# Relay.net
KiCad netlist of a schematic drawn in Altium Designer
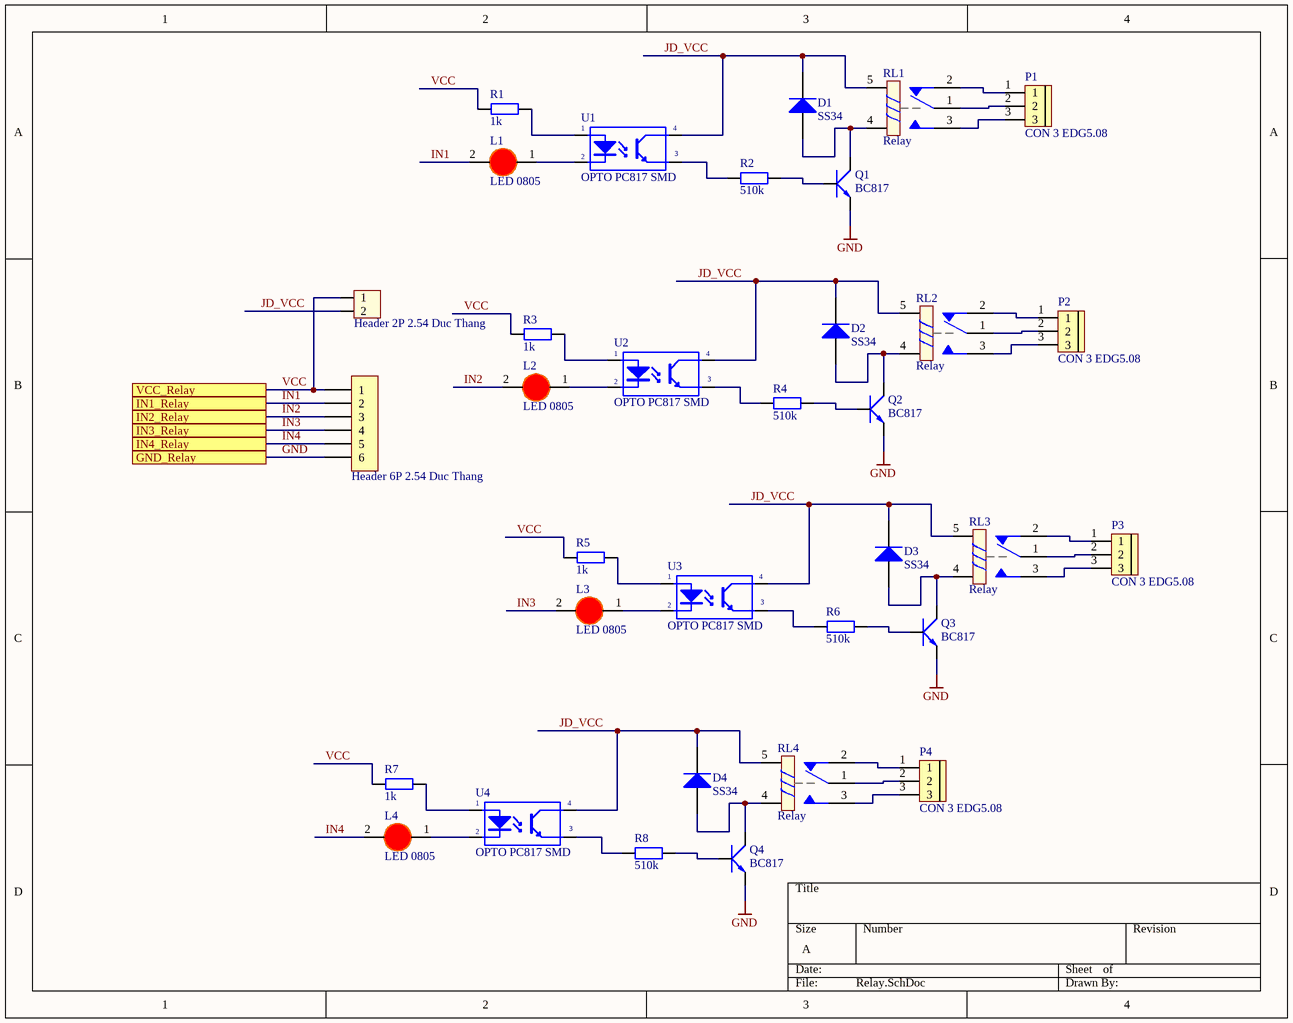
[diagram p0: Relay.SchDoc]

(export (version "E")
  (design (tool "Eeschema 10.0.6"))
  (components
    (comp (ref "D1")
      (value "SS34")
      (footprint "DIODE SMA")
      (description "Dán")
      (libsource (lib "Altium_Lib_by_KhueNguyenCreator") (part "Diode SS34 ( 1N5822 )"))
    )
    (comp (ref "D2")
      (value "SS34")
      (footprint "DIODE SMA")
      (description "Dán")
      (libsource (lib "Altium_Lib_by_KhueNguyenCreator") (part "Diode SS34 ( 1N5822 )"))
    )
    (comp (ref "D3")
      (value "SS34")
      (footprint "DIODE SMA")
      (description "Dán")
      (libsource (lib "Altium_Lib_by_KhueNguyenCreator") (part "Diode SS34 ( 1N5822 )"))
    )
    (comp (ref "D4")
      (value "SS34")
      (footprint "DIODE SMA")
      (description "Dán")
      (libsource (lib "Altium_Lib_by_KhueNguyenCreator") (part "Diode SS34 ( 1N5822 )"))
    )
    (comp (ref "H1")
      (value "Header 2P 2.54 Duc Thang")
      (footprint "XH2.54M-2")
      (description "Cắm")
      (libsource (lib "Altium_Lib_by_KhueNguyenCreator") (part "Header 2P 2.54 Duc Thang"))
    )
    (comp (ref "H2")
      (value "Header 6P 2.54 Duc Thang")
      (footprint "XH2.54M-6")
      (description "Cắm")
      (libsource (lib "Altium_Lib_by_KhueNguyenCreator") (part "Header 6P 2.54 Duc Thang"))
    )
    (comp (ref "L1")
      (value "LED 0805")
      (footprint "LED-0805-Red")
      (description "Dán")
      (libsource (lib "BKRES_Schlib") (part "LED 0805 Do"))
    )
    (comp (ref "L2")
      (value "LED 0805")
      (footprint "LED-0805-Red")
      (description "Dán")
      (libsource (lib "BKRES_Schlib") (part "LED 0805 Do"))
    )
    (comp (ref "L3")
      (value "LED 0805")
      (footprint "LED-0805-Red")
      (description "Dán")
      (libsource (lib "BKRES_Schlib") (part "LED 0805 Do"))
    )
    (comp (ref "L4")
      (value "LED 0805")
      (footprint "LED-0805-Red")
      (description "Dán")
      (libsource (lib "BKRES_Schlib") (part "LED 0805 Do"))
    )
    (comp (ref "P1")
      (value "CON 3 EDG5.08")
      (footprint "CON 3 3EDG5.08")
      (description "Cắm")
      (libsource (lib "Altium_Lib_by_KhueNguyenCreator") (part "CON 3 EDG5.08"))
    )
    (comp (ref "P2")
      (value "CON 3 EDG5.08")
      (footprint "CON 3 3EDG5.08")
      (description "Cắm")
      (libsource (lib "Altium_Lib_by_KhueNguyenCreator") (part "CON 3 EDG5.08"))
    )
    (comp (ref "P3")
      (value "CON 3 EDG5.08")
      (footprint "CON 3 3EDG5.08")
      (description "Cắm")
      (libsource (lib "Altium_Lib_by_KhueNguyenCreator") (part "CON 3 EDG5.08"))
    )
    (comp (ref "P4")
      (value "CON 3 EDG5.08")
      (footprint "CON 3 3EDG5.08")
      (description "Cắm")
      (libsource (lib "Altium_Lib_by_KhueNguyenCreator") (part "CON 3 EDG5.08"))
    )
    (comp (ref "Q1")
      (value "BC817")
      (footprint "SOT-23")
      (description "SOT-23 - C8658")
      (libsource (lib "Altium_Lib_by_KhueNguyenCreator") (part "Trans BC817"))
    )
    (comp (ref "Q2")
      (value "BC817")
      (footprint "SOT-23")
      (description "SOT-23 - C8658")
      (libsource (lib "Altium_Lib_by_KhueNguyenCreator") (part "Trans BC817"))
    )
    (comp (ref "Q3")
      (value "BC817")
      (footprint "SOT-23")
      (description "SOT-23 - C8658")
      (libsource (lib "Altium_Lib_by_KhueNguyenCreator") (part "Trans BC817"))
    )
    (comp (ref "Q4")
      (value "BC817")
      (footprint "SOT-23")
      (description "SOT-23 - C8658")
      (libsource (lib "Altium_Lib_by_KhueNguyenCreator") (part "Trans BC817"))
    )
    (comp (ref "R1")
      (value "1k")
      (footprint "tro smd 0805")
      (description "Dán")
      (libsource (lib "Altium_Lib_by_KhueNguyenCreator") (part "Tro 0805 1% 1k"))
    )
    (comp (ref "R2")
      (value "510k")
      (footprint "tro smd 0805")
      (description "Dán")
      (libsource (lib "Altium_Lib_by_KhueNguyenCreator") (part "Tro 0805 1% 510k"))
    )
    (comp (ref "R3")
      (value "1k")
      (footprint "tro smd 0805")
      (description "Dán")
      (libsource (lib "Altium_Lib_by_KhueNguyenCreator") (part "Tro 0805 1% 1k"))
    )
    (comp (ref "R4")
      (value "510k")
      (footprint "tro smd 0805")
      (description "Dán")
      (libsource (lib "Altium_Lib_by_KhueNguyenCreator") (part "Tro 0805 1% 510k"))
    )
    (comp (ref "R5")
      (value "1k")
      (footprint "tro smd 0805")
      (description "Dán")
      (libsource (lib "Altium_Lib_by_KhueNguyenCreator") (part "Tro 0805 1% 1k"))
    )
    (comp (ref "R6")
      (value "510k")
      (footprint "tro smd 0805")
      (description "Dán")
      (libsource (lib "Altium_Lib_by_KhueNguyenCreator") (part "Tro 0805 1% 510k"))
    )
    (comp (ref "R7")
      (value "1k")
      (footprint "tro smd 0805")
      (description "Dán")
      (libsource (lib "Altium_Lib_by_KhueNguyenCreator") (part "Tro 0805 1% 1k"))
    )
    (comp (ref "R8")
      (value "510k")
      (footprint "tro smd 0805")
      (description "Dán")
      (libsource (lib "Altium_Lib_by_KhueNguyenCreator") (part "Tro 0805 1% 510k"))
    )
    (comp (ref "RL1")
      (value "Relay")
      (footprint "Relay 5 Chan SRD")
      (description "Relay 5 Chan")
      (libsource (lib "Altium_Lib_by_KhueNguyenCreator") (part "Relay 5 Chan SRD"))
    )
    (comp (ref "RL2")
      (value "Relay")
      (footprint "Relay 5 Chan SRD")
      (description "Relay 5 Chan")
      (libsource (lib "Altium_Lib_by_KhueNguyenCreator") (part "Relay 5 Chan SRD"))
    )
    (comp (ref "RL3")
      (value "Relay")
      (footprint "Relay 5 Chan SRD")
      (description "Relay 5 Chan")
      (libsource (lib "Altium_Lib_by_KhueNguyenCreator") (part "Relay 5 Chan SRD"))
    )
    (comp (ref "RL4")
      (value "Relay")
      (footprint "Relay 5 Chan SRD")
      (description "Relay 5 Chan")
      (libsource (lib "Altium_Lib_by_KhueNguyenCreator") (part "Relay 5 Chan SRD"))
    )
    (comp (ref "U1")
      (value "OPTO PC817 SMD")
      (footprint "SOP4")
      (description "Single Opto")
      (libsource (lib "Altium_Lib_by_KhueNguyenCreator") (part "OPTO PC817 SMD"))
    )
    (comp (ref "U2")
      (value "OPTO PC817 SMD")
      (footprint "SOP4")
      (description "Single Opto")
      (libsource (lib "Altium_Lib_by_KhueNguyenCreator") (part "OPTO PC817 SMD"))
    )
    (comp (ref "U3")
      (value "OPTO PC817 SMD")
      (footprint "SOP4")
      (description "Single Opto")
      (libsource (lib "Altium_Lib_by_KhueNguyenCreator") (part "OPTO PC817 SMD"))
    )
    (comp (ref "U4")
      (value "OPTO PC817 SMD")
      (footprint "SOP4")
      (description "Single Opto")
      (libsource (lib "Altium_Lib_by_KhueNguyenCreator") (part "OPTO PC817 SMD"))
    )
  )
  (nets
    (net (code "1") (name "/IN1") (class "Default")
      (node (ref "H2") (pin "2") (pinfunction "2_2") (pintype "passive"))
      (node (ref "L1") (pin "2") (pinfunction "K_2") (pintype "passive"))
    )
    (net (code "2") (name "/IN2") (class "Default")
      (node (ref "H2") (pin "3") (pinfunction "3_3") (pintype "passive"))
      (node (ref "L2") (pin "2") (pinfunction "K_2") (pintype "passive"))
    )
    (net (code "3") (name "/IN3") (class "Default")
      (node (ref "H2") (pin "4") (pinfunction "4_4") (pintype "passive"))
      (node (ref "L3") (pin "2") (pinfunction "K_2") (pintype "passive"))
    )
    (net (code "4") (name "/IN4") (class "Default")
      (node (ref "H2") (pin "5") (pinfunction "5_5") (pintype "passive"))
      (node (ref "L4") (pin "2") (pinfunction "K_2") (pintype "passive"))
    )
    (net (code "5") (name "/JD_VCC") (class "Default")
      (node (ref "D1") (pin "2") (pinfunction "K_2") (pintype "passive"))
      (node (ref "D2") (pin "2") (pinfunction "K_2") (pintype "passive"))
      (node (ref "D3") (pin "2") (pinfunction "K_2") (pintype "passive"))
      (node (ref "D4") (pin "2") (pinfunction "K_2") (pintype "passive"))
      (node (ref "H1") (pin "2") (pinfunction "2_2") (pintype "passive"))
      (node (ref "RL1") (pin "5") (pinfunction "5_5") (pintype "passive"))
      (node (ref "RL2") (pin "5") (pinfunction "5_5") (pintype "passive"))
      (node (ref "RL3") (pin "5") (pinfunction "5_5") (pintype "passive"))
      (node (ref "RL4") (pin "5") (pinfunction "5_5") (pintype "passive"))
      (node (ref "U1") (pin "4") (pinfunction "C_4") (pintype "passive"))
      (node (ref "U2") (pin "4") (pinfunction "C_4") (pintype "passive"))
      (node (ref "U3") (pin "4") (pinfunction "C_4") (pintype "passive"))
      (node (ref "U4") (pin "4") (pinfunction "C_4") (pintype "passive"))
    )
    (net (code "6") (name "/VCC") (class "Default")
      (node (ref "H1") (pin "1") (pinfunction "1_1") (pintype "passive"))
      (node (ref "H2") (pin "1") (pinfunction "1_1") (pintype "passive"))
      (node (ref "R1") (pin "2") (pinfunction "2_2") (pintype "passive"))
      (node (ref "R3") (pin "2") (pinfunction "2_2") (pintype "passive"))
      (node (ref "R5") (pin "2") (pinfunction "2_2") (pintype "passive"))
      (node (ref "R7") (pin "2") (pinfunction "2_2") (pintype "passive"))
    )
    (net (code "7") (name "GND") (class "Default")
      (node (ref "H2") (pin "6") (pinfunction "6_6") (pintype "passive"))
      (node (ref "Q1") (pin "2") (pinfunction "E_2") (pintype "passive"))
      (node (ref "Q2") (pin "2") (pinfunction "E_2") (pintype "passive"))
      (node (ref "Q3") (pin "2") (pinfunction "E_2") (pintype "passive"))
      (node (ref "Q4") (pin "2") (pinfunction "E_2") (pintype "passive"))
    )
    (net (code "8") (name "Net-(D1-A)") (class "Default")
      (node (ref "D1") (pin "1") (pinfunction "A_1") (pintype "passive"))
      (node (ref "Q1") (pin "3") (pinfunction "C_3") (pintype "passive"))
      (node (ref "RL1") (pin "4") (pinfunction "4_4") (pintype "passive"))
    )
    (net (code "9") (name "Net-(D2-A)") (class "Default")
      (node (ref "D2") (pin "1") (pinfunction "A_1") (pintype "passive"))
      (node (ref "Q2") (pin "3") (pinfunction "C_3") (pintype "passive"))
      (node (ref "RL2") (pin "4") (pinfunction "4_4") (pintype "passive"))
    )
    (net (code "10") (name "Net-(D3-A)") (class "Default")
      (node (ref "D3") (pin "1") (pinfunction "A_1") (pintype "passive"))
      (node (ref "Q3") (pin "3") (pinfunction "C_3") (pintype "passive"))
      (node (ref "RL3") (pin "4") (pinfunction "4_4") (pintype "passive"))
    )
    (net (code "11") (name "Net-(D4-A)") (class "Default")
      (node (ref "D4") (pin "1") (pinfunction "A_1") (pintype "passive"))
      (node (ref "Q4") (pin "3") (pinfunction "C_3") (pintype "passive"))
      (node (ref "RL4") (pin "4") (pinfunction "4_4") (pintype "passive"))
    )
    (net (code "12") (name "Net-(L1-A)") (class "Default")
      (node (ref "L1") (pin "1") (pinfunction "A_1") (pintype "passive"))
      (node (ref "U1") (pin "2") (pinfunction "K_2") (pintype "passive"))
    )
    (net (code "13") (name "Net-(L2-A)") (class "Default")
      (node (ref "L2") (pin "1") (pinfunction "A_1") (pintype "passive"))
      (node (ref "U2") (pin "2") (pinfunction "K_2") (pintype "passive"))
    )
    (net (code "14") (name "Net-(L3-A)") (class "Default")
      (node (ref "L3") (pin "1") (pinfunction "A_1") (pintype "passive"))
      (node (ref "U3") (pin "2") (pinfunction "K_2") (pintype "passive"))
    )
    (net (code "15") (name "Net-(L4-A)") (class "Default")
      (node (ref "L4") (pin "1") (pinfunction "A_1") (pintype "passive"))
      (node (ref "U4") (pin "2") (pinfunction "K_2") (pintype "passive"))
    )
    (net (code "16") (name "Net-(P1-Pad1)") (class "Default")
      (node (ref "P1") (pin "1") (pinfunction "1_1") (pintype "passive"))
      (node (ref "RL1") (pin "2") (pinfunction "2_2") (pintype "passive"))
    )
    (net (code "17") (name "Net-(P1-Pad2)") (class "Default")
      (node (ref "P1") (pin "2") (pinfunction "2_2") (pintype "passive"))
      (node (ref "RL1") (pin "1") (pinfunction "1_1") (pintype "passive"))
    )
    (net (code "18") (name "Net-(P1-Pad3)") (class "Default")
      (node (ref "P1") (pin "3") (pinfunction "3_3") (pintype "passive"))
      (node (ref "RL1") (pin "3") (pinfunction "3_3") (pintype "passive"))
    )
    (net (code "19") (name "Net-(P2-Pad1)") (class "Default")
      (node (ref "P2") (pin "1") (pinfunction "1_1") (pintype "passive"))
      (node (ref "RL2") (pin "2") (pinfunction "2_2") (pintype "passive"))
    )
    (net (code "20") (name "Net-(P2-Pad2)") (class "Default")
      (node (ref "P2") (pin "2") (pinfunction "2_2") (pintype "passive"))
      (node (ref "RL2") (pin "1") (pinfunction "1_1") (pintype "passive"))
    )
    (net (code "21") (name "Net-(P2-Pad3)") (class "Default")
      (node (ref "P2") (pin "3") (pinfunction "3_3") (pintype "passive"))
      (node (ref "RL2") (pin "3") (pinfunction "3_3") (pintype "passive"))
    )
    (net (code "22") (name "Net-(P3-Pad1)") (class "Default")
      (node (ref "P3") (pin "1") (pinfunction "1_1") (pintype "passive"))
      (node (ref "RL3") (pin "2") (pinfunction "2_2") (pintype "passive"))
    )
    (net (code "23") (name "Net-(P3-Pad2)") (class "Default")
      (node (ref "P3") (pin "2") (pinfunction "2_2") (pintype "passive"))
      (node (ref "RL3") (pin "1") (pinfunction "1_1") (pintype "passive"))
    )
    (net (code "24") (name "Net-(P3-Pad3)") (class "Default")
      (node (ref "P3") (pin "3") (pinfunction "3_3") (pintype "passive"))
      (node (ref "RL3") (pin "3") (pinfunction "3_3") (pintype "passive"))
    )
    (net (code "25") (name "Net-(P4-Pad1)") (class "Default")
      (node (ref "P4") (pin "1") (pinfunction "1_1") (pintype "passive"))
      (node (ref "RL4") (pin "2") (pinfunction "2_2") (pintype "passive"))
    )
    (net (code "26") (name "Net-(P4-Pad2)") (class "Default")
      (node (ref "P4") (pin "2") (pinfunction "2_2") (pintype "passive"))
      (node (ref "RL4") (pin "1") (pinfunction "1_1") (pintype "passive"))
    )
    (net (code "27") (name "Net-(P4-Pad3)") (class "Default")
      (node (ref "P4") (pin "3") (pinfunction "3_3") (pintype "passive"))
      (node (ref "RL4") (pin "3") (pinfunction "3_3") (pintype "passive"))
    )
    (net (code "28") (name "Net-(Q1-B)") (class "Default")
      (node (ref "Q1") (pin "1") (pinfunction "B_1") (pintype "passive"))
      (node (ref "R2") (pin "2") (pinfunction "2_2") (pintype "passive"))
    )
    (net (code "29") (name "Net-(Q2-B)") (class "Default")
      (node (ref "Q2") (pin "1") (pinfunction "B_1") (pintype "passive"))
      (node (ref "R4") (pin "2") (pinfunction "2_2") (pintype "passive"))
    )
    (net (code "30") (name "Net-(Q3-B)") (class "Default")
      (node (ref "Q3") (pin "1") (pinfunction "B_1") (pintype "passive"))
      (node (ref "R6") (pin "2") (pinfunction "2_2") (pintype "passive"))
    )
    (net (code "31") (name "Net-(Q4-B)") (class "Default")
      (node (ref "Q4") (pin "1") (pinfunction "B_1") (pintype "passive"))
      (node (ref "R8") (pin "2") (pinfunction "2_2") (pintype "passive"))
    )
    (net (code "32") (name "Net-(U1-A)") (class "Default")
      (node (ref "R1") (pin "1") (pinfunction "1_1") (pintype "passive"))
      (node (ref "U1") (pin "1") (pinfunction "A_1") (pintype "passive"))
    )
    (net (code "33") (name "Net-(U1-E)") (class "Default")
      (node (ref "R2") (pin "1") (pinfunction "1_1") (pintype "passive"))
      (node (ref "U1") (pin "3") (pinfunction "E_3") (pintype "passive"))
    )
    (net (code "34") (name "Net-(U2-A)") (class "Default")
      (node (ref "R3") (pin "1") (pinfunction "1_1") (pintype "passive"))
      (node (ref "U2") (pin "1") (pinfunction "A_1") (pintype "passive"))
    )
    (net (code "35") (name "Net-(U2-E)") (class "Default")
      (node (ref "R4") (pin "1") (pinfunction "1_1") (pintype "passive"))
      (node (ref "U2") (pin "3") (pinfunction "E_3") (pintype "passive"))
    )
    (net (code "36") (name "Net-(U3-A)") (class "Default")
      (node (ref "R5") (pin "1") (pinfunction "1_1") (pintype "passive"))
      (node (ref "U3") (pin "1") (pinfunction "A_1") (pintype "passive"))
    )
    (net (code "37") (name "Net-(U3-E)") (class "Default")
      (node (ref "R6") (pin "1") (pinfunction "1_1") (pintype "passive"))
      (node (ref "U3") (pin "3") (pinfunction "E_3") (pintype "passive"))
    )
    (net (code "38") (name "Net-(U4-A)") (class "Default")
      (node (ref "R7") (pin "1") (pinfunction "1_1") (pintype "passive"))
      (node (ref "U4") (pin "1") (pinfunction "A_1") (pintype "passive"))
    )
    (net (code "39") (name "Net-(U4-E)") (class "Default")
      (node (ref "R8") (pin "1") (pinfunction "1_1") (pintype "passive"))
      (node (ref "U4") (pin "3") (pinfunction "E_3") (pintype "passive"))
    )
  )
)
